# main.net
KiCad netlist of a schematic drawn in EAGLE
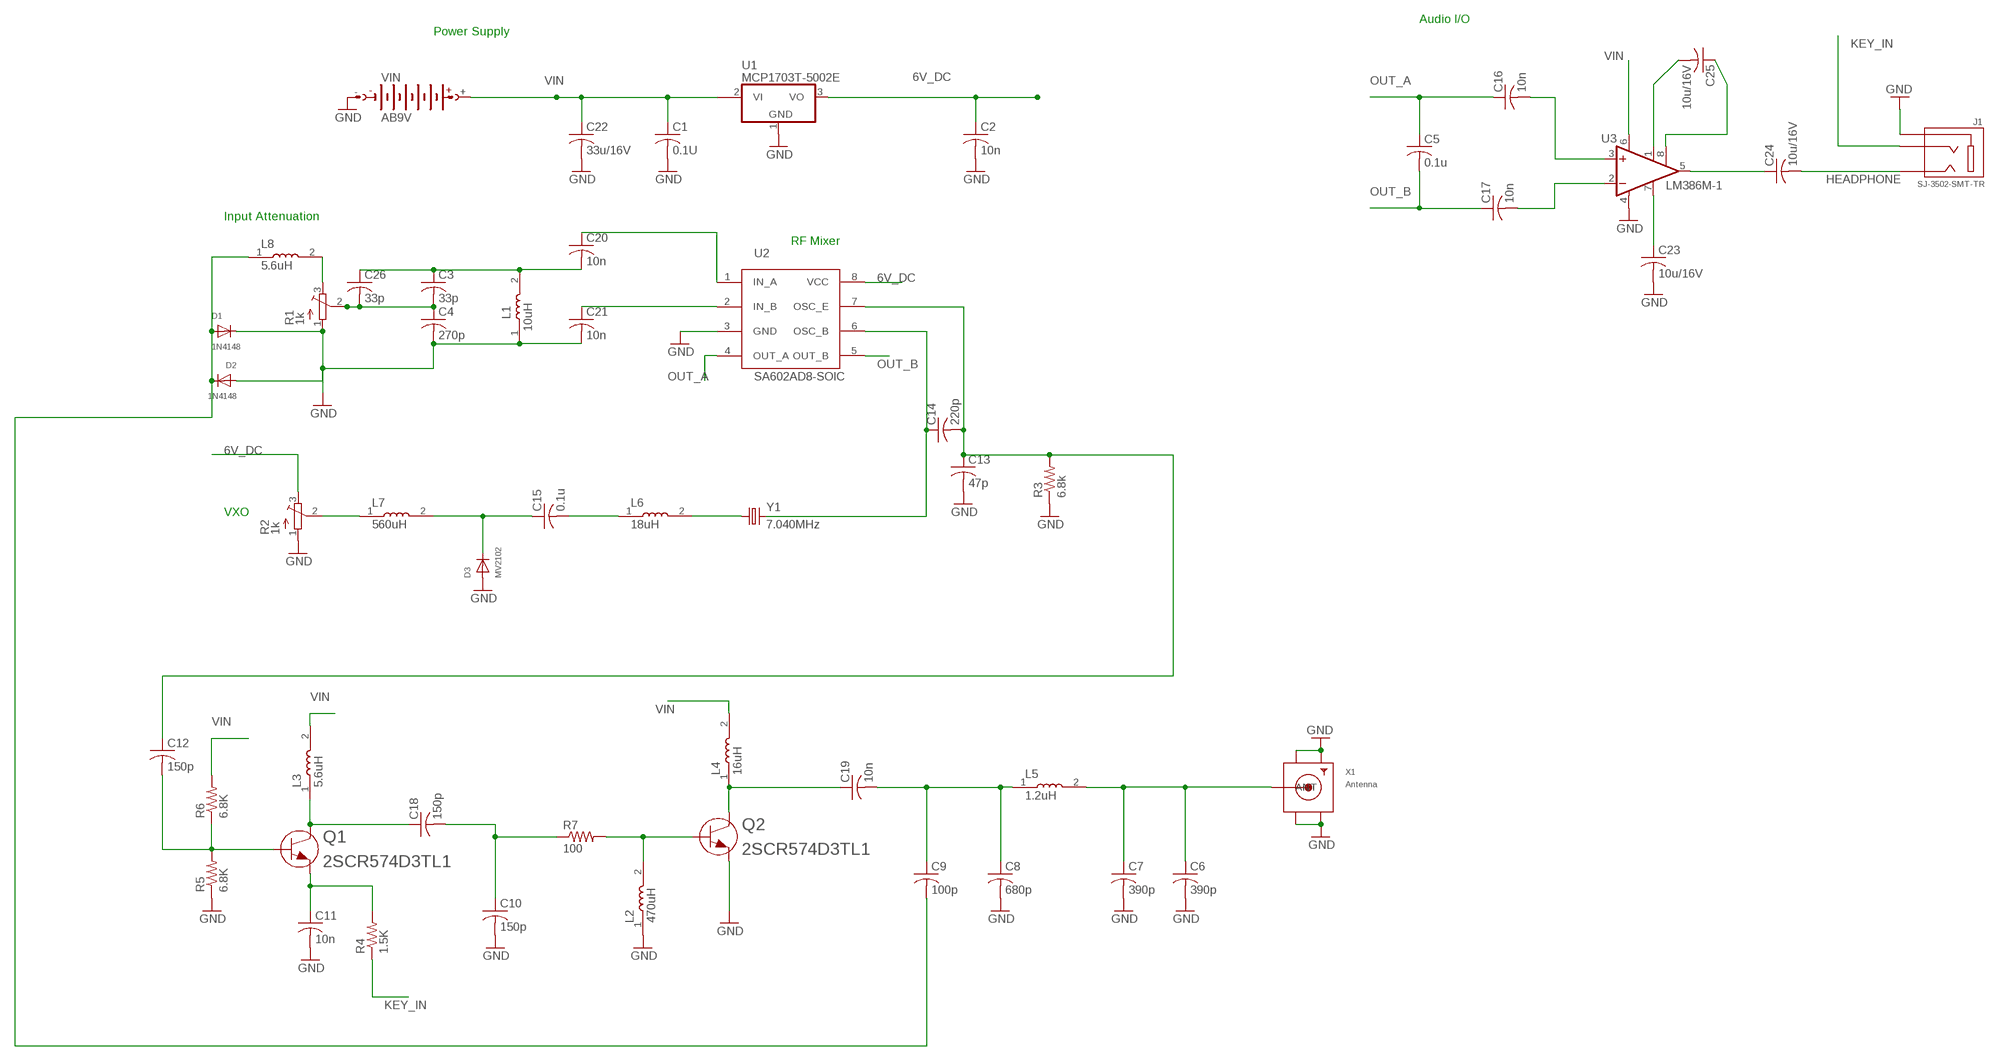
[diagram p0: schematic, sheet 1]

(export (version "E")
  (design (tool "Eeschema 10.0.6"))
  (components
    (comp (ref "C1")
      (value "0.1U")
      (footprint "eagle-import:C0805")
      (libsource (lib "eagle-import") (part "C-USC0805"))
    )
    (comp (ref "C2")
      (value "10n")
      (footprint "eagle-import:C0805")
      (libsource (lib "eagle-import") (part "C-USC0805"))
    )
    (comp (ref "C3")
      (value "33p")
      (footprint "eagle-import:C0805")
      (libsource (lib "eagle-import") (part "C-USC0805"))
    )
    (comp (ref "C4")
      (value "270p")
      (footprint "eagle-import:C0805")
      (libsource (lib "eagle-import") (part "C-USC0805"))
    )
    (comp (ref "C5")
      (value "0.1u")
      (footprint "eagle-import:C0805")
      (libsource (lib "eagle-import") (part "C-USC0805"))
    )
    (comp (ref "C6")
      (value "390p")
      (footprint "eagle-import:C0805")
      (libsource (lib "eagle-import") (part "C-USC0805"))
    )
    (comp (ref "C7")
      (value "390p")
      (footprint "eagle-import:C0805")
      (libsource (lib "eagle-import") (part "C-USC0805"))
    )
    (comp (ref "C8")
      (value "680p")
      (footprint "eagle-import:C0805")
      (libsource (lib "eagle-import") (part "C-USC0805"))
    )
    (comp (ref "C9")
      (value "100p")
      (footprint "eagle-import:C0805")
      (libsource (lib "eagle-import") (part "C-USC0805"))
    )
    (comp (ref "C10")
      (value "150p")
      (footprint "eagle-import:C0805")
      (libsource (lib "eagle-import") (part "C-USC0805"))
    )
    (comp (ref "C11")
      (value "10n")
      (footprint "eagle-import:C0805")
      (libsource (lib "eagle-import") (part "C-USC0805"))
    )
    (comp (ref "C12")
      (value "150p")
      (footprint "eagle-import:C0805")
      (libsource (lib "eagle-import") (part "C-USC0805"))
    )
    (comp (ref "C13")
      (value "47p")
      (footprint "eagle-import:C0805")
      (libsource (lib "eagle-import") (part "C-USC0805"))
    )
    (comp (ref "C14")
      (value "220p")
      (footprint "eagle-import:C0805")
      (libsource (lib "eagle-import") (part "C-USC0805"))
    )
    (comp (ref "C15")
      (value "0.1u")
      (footprint "eagle-import:C0805")
      (libsource (lib "eagle-import") (part "C-USC0805"))
    )
    (comp (ref "C16")
      (value "10n")
      (footprint "eagle-import:C0805")
      (libsource (lib "eagle-import") (part "C-USC0805"))
    )
    (comp (ref "C17")
      (value "10n")
      (footprint "eagle-import:C0805")
      (libsource (lib "eagle-import") (part "C-USC0805"))
    )
    (comp (ref "C18")
      (value "150p")
      (footprint "eagle-import:C0805")
      (libsource (lib "eagle-import") (part "C-USC0805"))
    )
    (comp (ref "C19")
      (value "10n")
      (footprint "eagle-import:C0805")
      (libsource (lib "eagle-import") (part "C-USC0805"))
    )
    (comp (ref "C20")
      (value "10n")
      (footprint "eagle-import:C0805")
      (libsource (lib "eagle-import") (part "C-USC0805"))
    )
    (comp (ref "C21")
      (value "10n")
      (footprint "eagle-import:C0805")
      (libsource (lib "eagle-import") (part "C-USC0805"))
    )
    (comp (ref "C22")
      (value "33u/16V")
      (footprint "eagle-import:C0805")
      (libsource (lib "eagle-import") (part "C-USC0805"))
    )
    (comp (ref "C23")
      (value "10u/16V")
      (footprint "eagle-import:C0805")
      (libsource (lib "eagle-import") (part "C-USC0805"))
    )
    (comp (ref "C24")
      (value "10u/16V")
      (footprint "eagle-import:C0805")
      (libsource (lib "eagle-import") (part "C-USC0805"))
    )
    (comp (ref "C25")
      (value "10u/16V")
      (footprint "eagle-import:C0805")
      (libsource (lib "eagle-import") (part "C-USC0805"))
    )
    (comp (ref "C26")
      (value "33p")
      (footprint "eagle-import:C0805")
      (libsource (lib "eagle-import") (part "C-USC0805"))
    )
    (comp (ref "D1")
      (value "1N4148")
      (footprint "eagle-import:SOD-123FL")
      (libsource (lib "eagle-import") (part "DIODE_SOD-123FL"))
    )
    (comp (ref "D2")
      (value "1N4148")
      (footprint "eagle-import:SOD-123FL")
      (libsource (lib "eagle-import") (part "DIODE_SOD-123FL"))
    )
    (comp (ref "D3")
      (value "MV2102")
      (footprint "eagle-import:SOD-323F")
      (libsource (lib "eagle-import") (part "DIODESOD-323F"))
    )
    (comp (ref "J1")
      (value "SJ-3502-SMT-TR")
      (footprint "eagle-import:SJ-3502-SMT-TR")
      (fields
        (field (name "DIGIKEY_PARTNO") "CP-3502SJTR-ND")
        (field (name "MANUFACTURER") "CUI Devices")
        (field (name "CREATED_BY") "PCBLayout.com")
      )
      (libsource (lib "eagle-import") (part "SJ-3502-SMT-TR"))
    )
    (comp (ref "L1")
      (value "10uH")
      (footprint "eagle-import:INDC2012X87N")
      (fields (field (name "MF") "TDK") (field (name "MP") "MLF2012E5R6KT000"))
      (libsource (lib "eagle-import") (part "MLF2012E5R6KT000"))
    )
    (comp (ref "L2")
      (value "470uH")
      (footprint "eagle-import:INDC2012X87N")
      (fields (field (name "MF") "TDK") (field (name "MP") "MLF2012E5R6KT000"))
      (libsource (lib "eagle-import") (part "MLF2012E5R6KT000"))
    )
    (comp (ref "L3")
      (value "5.6uH")
      (footprint "eagle-import:INDC2012X87N")
      (fields (field (name "MF") "TDK") (field (name "MP") "MLF2012E5R6KT000"))
      (libsource (lib "eagle-import") (part "MLF2012E5R6KT000"))
    )
    (comp (ref "L4")
      (value "16uH")
      (footprint "eagle-import:INDC2012X87N")
      (fields (field (name "MF") "TDK") (field (name "MP") "MLF2012E5R6KT000"))
      (libsource (lib "eagle-import") (part "MLF2012E5R6KT000"))
    )
    (comp (ref "L5")
      (value "1.2uH")
      (footprint "eagle-import:INDC2012X87N")
      (fields (field (name "MF") "TDK") (field (name "MP") "MLF2012E5R6KT000"))
      (libsource (lib "eagle-import") (part "MLF2012E5R6KT000"))
    )
    (comp (ref "L6")
      (value "18uH")
      (footprint "eagle-import:INDC2012X87N")
      (fields (field (name "MF") "TDK") (field (name "MP") "MLF2012E5R6KT000"))
      (libsource (lib "eagle-import") (part "MLF2012E5R6KT000"))
    )
    (comp (ref "L7")
      (value "560uH")
      (footprint "eagle-import:INDC2012X87N")
      (fields (field (name "MF") "TDK") (field (name "MP") "MLF2012E5R6KT000"))
      (libsource (lib "eagle-import") (part "MLF2012E5R6KT000"))
    )
    (comp (ref "L8")
      (value "5.6uH")
      (footprint "eagle-import:INDC2012X87N")
      (fields (field (name "MF") "TDK") (field (name "MP") "MLF2012E5R6KT000"))
      (libsource (lib "eagle-import") (part "MLF2012E5R6KT000"))
    )
    (comp (ref "Q1")
      (value "2SCR574D3TL1")
      (footprint "eagle-import:TRANS_2SCR573D_ROM")
      (fields (field (name "COPYRIGHT") "Copyright (C) 2018 Accelerated Designs. All rights reserved"))
      (libsource (lib "eagle-import") (part "2SCR574D3TL1"))
    )
    (comp (ref "Q2")
      (value "2SCR574D3TL1")
      (footprint "eagle-import:TRANS_2SCR573D_ROM")
      (fields (field (name "COPYRIGHT") "Copyright (C) 2018 Accelerated Designs. All rights reserved"))
      (libsource (lib "eagle-import") (part "2SCR574D3TL1"))
    )
    (comp (ref "R1")
      (value "1k")
      (footprint "eagle-import:3223G")
      (libsource (lib "eagle-import") (part "TRIM_EU-3223G"))
    )
    (comp (ref "R2")
      (value "1k")
      (footprint "eagle-import:3223G")
      (libsource (lib "eagle-import") (part "TRIM_EU-3223G"))
    )
    (comp (ref "R3")
      (value "6.8k")
      (footprint "eagle-import:M0805")
      (libsource (lib "eagle-import") (part "R-US_M0805"))
    )
    (comp (ref "R4")
      (value "1.5K")
      (footprint "eagle-import:M0805")
      (libsource (lib "eagle-import") (part "R-US_M0805"))
    )
    (comp (ref "R5")
      (value "6.8K")
      (footprint "eagle-import:M0805")
      (libsource (lib "eagle-import") (part "R-US_M0805"))
    )
    (comp (ref "R6")
      (value "6.8K")
      (footprint "eagle-import:M0805")
      (libsource (lib "eagle-import") (part "R-US_M0805"))
    )
    (comp (ref "R7")
      (value "100")
      (footprint "eagle-import:M0805")
      (libsource (lib "eagle-import") (part "R-US_M0805"))
    )
    (comp (ref "U1")
      (value "MCP1703T-5002E")
      (footprint "eagle-import:SOT89")
      (libsource (lib "eagle-import") (part "MCP1703MB12"))
    )
    (comp (ref "U2")
      (value "SA602AD8-SOIC")
      (footprint "eagle-import:SOIC127P599X175-8N")
      (libsource (lib "eagle-import") (part "SA602AD8-SOIC"))
    )
    (comp (ref "U3")
      (value "LM386M-1")
      (footprint "eagle-import:SO08")
      (libsource (lib "eagle-import") (part "LM386?-M1"))
    )
    (comp (ref "VIN")
      (value "AB9V")
      (footprint "eagle-import:AB9V")
      (libsource (lib "eagle-import") (part "AB9V"))
    )
    (comp (ref "X1")
      (value "Antenna")
      (footprint "eagle-import:SMA_EDGELAUNCH")
      (libsource (lib "eagle-import") (part "SMACONNECTOR_EDGE"))
    )
    (comp (ref "Y1")
      (value "7.040MHz")
      (footprint "eagle-import:CTS406")
      (libsource (lib "eagle-import") (part "CRYSTALCTS406"))
    )
  )
  (nets
    (net (code "1") (name "/6V_DC") (class "Default")
      (node (ref "C2") (pin "1") (pinfunction "1_1") (pintype "passive"))
      (node (ref "R2") (pin "3") (pinfunction "E_3") (pintype "passive"))
      (node (ref "U1") (pin "3") (pinfunction "VO_3") (pintype "passive"))
      (node (ref "U2") (pin "8") (pinfunction "VCC_8") (pintype "bidirectional"))
    )
    (net (code "2") (name "/HEADPHONE") (class "Default")
      (node (ref "C24") (pin "2") (pinfunction "2_2") (pintype "passive"))
      (node (ref "J1") (pin "2") (pinfunction "2_2") (pintype "passive"))
    )
    (net (code "3") (name "/KEY_IN") (class "Default")
      (node (ref "J1") (pin "3") (pinfunction "3_3") (pintype "passive"))
      (node (ref "R4") (pin "1") (pinfunction "1_1") (pintype "passive"))
    )
    (net (code "4") (name "/OUT_A") (class "Default")
      (node (ref "C16") (pin "1") (pinfunction "1_1") (pintype "passive"))
      (node (ref "C5") (pin "1") (pinfunction "1_1") (pintype "passive"))
      (node (ref "U2") (pin "4") (pinfunction "OUT_A_4") (pintype "bidirectional"))
    )
    (net (code "5") (name "/OUT_B") (class "Default")
      (node (ref "C17") (pin "1") (pinfunction "1_1") (pintype "passive"))
      (node (ref "C5") (pin "2") (pinfunction "2_2") (pintype "passive"))
      (node (ref "U2") (pin "5") (pinfunction "OUT_B_5") (pintype "bidirectional"))
    )
    (net (code "6") (name "/VIN") (class "Default")
      (node (ref "C1") (pin "1") (pinfunction "1_1") (pintype "passive"))
      (node (ref "C22") (pin "1") (pinfunction "1_1") (pintype "passive"))
      (node (ref "L3") (pin "2") (pinfunction "2_2") (pintype "passive"))
      (node (ref "L4") (pin "2") (pinfunction "2_2") (pintype "passive"))
      (node (ref "R6") (pin "2") (pinfunction "2_2") (pintype "passive"))
      (node (ref "U1") (pin "2@1") (pinfunction "VI1_2@1") (pintype "input"))
      (node (ref "U3") (pin "6") (pinfunction "VS_6") (pintype "power_in"))
      (node (ref "VIN") (pin "+") (pinfunction "+_+") (pintype "passive"))
    )
    (net (code "7") (name "GND") (class "Default")
      (node (ref "C1") (pin "2") (pinfunction "2_2") (pintype "passive"))
      (node (ref "C10") (pin "2") (pinfunction "2_2") (pintype "passive"))
      (node (ref "C11") (pin "2") (pinfunction "2_2") (pintype "passive"))
      (node (ref "C13") (pin "2") (pinfunction "2_2") (pintype "passive"))
      (node (ref "C2") (pin "2") (pinfunction "2_2") (pintype "passive"))
      (node (ref "C21") (pin "2") (pinfunction "2_2") (pintype "passive"))
      (node (ref "C22") (pin "2") (pinfunction "2_2") (pintype "passive"))
      (node (ref "C23") (pin "2") (pinfunction "2_2") (pintype "passive"))
      (node (ref "C4") (pin "2") (pinfunction "2_2") (pintype "passive"))
      (node (ref "C6") (pin "2") (pinfunction "2_2") (pintype "passive"))
      (node (ref "C7") (pin "2") (pinfunction "2_2") (pintype "passive"))
      (node (ref "C8") (pin "2") (pinfunction "2_2") (pintype "passive"))
      (node (ref "D1") (pin "C") (pinfunction "C_C") (pintype "passive"))
      (node (ref "D2") (pin "A") (pinfunction "A_A") (pintype "passive"))
      (node (ref "D3") (pin "A") (pinfunction "A_A") (pintype "passive"))
      (node (ref "J1") (pin "1_1") (pinfunction "1_1_1") (pintype "passive"))
      (node (ref "J1") (pin "1_2") (pinfunction "1_1_2") (pintype "passive"))
      (node (ref "J1") (pin "1_3") (pinfunction "1_1_3") (pintype "passive"))
      (node (ref "J1") (pin "1_4") (pinfunction "1_1_4") (pintype "passive"))
      (node (ref "L1") (pin "1") (pinfunction "1_1") (pintype "passive"))
      (node (ref "L2") (pin "1") (pinfunction "1_1") (pintype "passive"))
      (node (ref "Q2") (pin "3") (pinfunction "3_3") (pintype "passive"))
      (node (ref "R1") (pin "1") (pinfunction "A_1") (pintype "passive"))
      (node (ref "R2") (pin "1") (pinfunction "A_1") (pintype "passive"))
      (node (ref "R3") (pin "1") (pinfunction "1_1") (pintype "passive"))
      (node (ref "R5") (pin "1") (pinfunction "1_1") (pintype "passive"))
      (node (ref "U1") (pin "1") (pinfunction "GND_1") (pintype "passive"))
      (node (ref "U2") (pin "3") (pinfunction "GND_3") (pintype "bidirectional"))
      (node (ref "U3") (pin "4") (pinfunction "GND_4") (pintype "power_in"))
      (node (ref "VIN") (pin "-") (pinfunction "-_-") (pintype "passive"))
      (node (ref "X1") (pin "GND@1") (pinfunction "GND4_GND@1") (pintype "power_in"))
      (node (ref "X1") (pin "GND@2") (pinfunction "GND3_GND@2") (pintype "power_in"))
      (node (ref "X1") (pin "GND@3") (pinfunction "GND2_GND@3") (pintype "power_in"))
      (node (ref "X1") (pin "GND@4") (pinfunction "GND1_GND@4") (pintype "power_in"))
    )
    (net (code "8") (name "Net-(C9-Pad2)") (class "Default")
      (node (ref "C9") (pin "2") (pinfunction "2_2") (pintype "passive"))
      (node (ref "D1") (pin "A") (pinfunction "A_A") (pintype "passive"))
      (node (ref "D2") (pin "C") (pinfunction "C_C") (pintype "passive"))
      (node (ref "L8") (pin "1") (pinfunction "1_1") (pintype "passive"))
    )
    (net (code "9") (name "Net-(C10-Pad1)") (class "Default")
      (node (ref "C10") (pin "1") (pinfunction "1_1") (pintype "passive"))
      (node (ref "C18") (pin "2") (pinfunction "2_2") (pintype "passive"))
      (node (ref "R7") (pin "1") (pinfunction "1_1") (pintype "passive"))
    )
    (net (code "10") (name "Net-(C11-Pad1)") (class "Default")
      (node (ref "C11") (pin "1") (pinfunction "1_1") (pintype "passive"))
      (node (ref "Q1") (pin "3") (pinfunction "3_3") (pintype "passive"))
      (node (ref "R4") (pin "2") (pinfunction "2_2") (pintype "passive"))
    )
    (net (code "11") (name "Net-(C12-Pad2)") (class "Default")
      (node (ref "C12") (pin "2") (pinfunction "2_2") (pintype "passive"))
      (node (ref "Q1") (pin "1") (pinfunction "1_1") (pintype "passive"))
      (node (ref "R5") (pin "2") (pinfunction "2_2") (pintype "passive"))
      (node (ref "R6") (pin "1") (pinfunction "1_1") (pintype "passive"))
    )
    (net (code "12") (name "Net-(C15-Pad1)") (class "Default")
      (node (ref "C15") (pin "1") (pinfunction "1_1") (pintype "passive"))
      (node (ref "D3") (pin "C") (pinfunction "C_C") (pintype "passive"))
      (node (ref "L7") (pin "2") (pinfunction "2_2") (pintype "passive"))
    )
    (net (code "13") (name "Net-(C15-Pad2)") (class "Default")
      (node (ref "C15") (pin "2") (pinfunction "2_2") (pintype "passive"))
      (node (ref "L6") (pin "1") (pinfunction "1_1") (pintype "passive"))
    )
    (net (code "14") (name "Net-(C18-Pad1)") (class "Default")
      (node (ref "C18") (pin "1") (pinfunction "1_1") (pintype "passive"))
      (node (ref "L3") (pin "1") (pinfunction "1_1") (pintype "passive"))
      (node (ref "Q1") (pin "2") (pinfunction "2_2") (pintype "passive"))
    )
    (net (code "15") (name "Net-(C19-Pad1)") (class "Default")
      (node (ref "C19") (pin "1") (pinfunction "1_1") (pintype "passive"))
      (node (ref "L4") (pin "1") (pinfunction "1_1") (pintype "passive"))
      (node (ref "Q2") (pin "2") (pinfunction "2_2") (pintype "passive"))
    )
    (net (code "16") (name "Net-(C19-Pad2)") (class "Default")
      (node (ref "C19") (pin "2") (pinfunction "2_2") (pintype "passive"))
      (node (ref "C8") (pin "1") (pinfunction "1_1") (pintype "passive"))
      (node (ref "C9") (pin "1") (pinfunction "1_1") (pintype "passive"))
      (node (ref "L5") (pin "1") (pinfunction "1_1") (pintype "passive"))
    )
    (net (code "17") (name "Net-(C20-Pad2)") (class "Default")
      (node (ref "C20") (pin "2") (pinfunction "2_2") (pintype "passive"))
      (node (ref "C26") (pin "1") (pinfunction "1_1") (pintype "passive"))
      (node (ref "C3") (pin "1") (pinfunction "1_1") (pintype "passive"))
      (node (ref "L1") (pin "2") (pinfunction "2_2") (pintype "passive"))
    )
    (net (code "18") (name "Net-(C25-Pad1)") (class "Default")
      (node (ref "C25") (pin "1") (pinfunction "1_1") (pintype "passive"))
      (node (ref "U3") (pin "8") (pinfunction "GAIN_8") (pintype "passive"))
    )
    (net (code "19") (name "Net-(C25-Pad2)") (class "Default")
      (node (ref "C25") (pin "2") (pinfunction "2_2") (pintype "passive"))
      (node (ref "U3") (pin "1") (pinfunction "GAIN_1") (pintype "passive"))
    )
    (net (code "20") (name "Net-(L2-Pad2)") (class "Default")
      (node (ref "L2") (pin "2") (pinfunction "2_2") (pintype "passive"))
      (node (ref "Q2") (pin "1") (pinfunction "1_1") (pintype "passive"))
      (node (ref "R7") (pin "2") (pinfunction "2_2") (pintype "passive"))
    )
    (net (code "21") (name "Net-(L6-Pad2)") (class "Default")
      (node (ref "L6") (pin "2") (pinfunction "2_2") (pintype "passive"))
      (node (ref "Y1") (pin "1") (pinfunction "1_1") (pintype "passive"))
    )
    (net (code "22") (name "Net-(R1-E)") (class "Default")
      (node (ref "L8") (pin "2") (pinfunction "2_2") (pintype "passive"))
      (node (ref "R1") (pin "3") (pinfunction "E_3") (pintype "passive"))
    )
    (net (code "23") (name "Net-(R1-S)") (class "Default")
      (node (ref "C26") (pin "2") (pinfunction "2_2") (pintype "passive"))
      (node (ref "C3") (pin "2") (pinfunction "2_2") (pintype "passive"))
      (node (ref "C4") (pin "1") (pinfunction "1_1") (pintype "passive"))
      (node (ref "R1") (pin "2") (pinfunction "S_2") (pintype "passive"))
    )
    (net (code "24") (name "Net-(R2-S)") (class "Default")
      (node (ref "L7") (pin "1") (pinfunction "1_1") (pintype "passive"))
      (node (ref "R2") (pin "2") (pinfunction "S_2") (pintype "passive"))
    )
    (net (code "25") (name "Net-(U2-IN_A)") (class "Default")
      (node (ref "C20") (pin "1") (pinfunction "1_1") (pintype "passive"))
      (node (ref "U2") (pin "1") (pinfunction "IN_A_1") (pintype "bidirectional"))
    )
    (net (code "26") (name "Net-(U2-IN_B)") (class "Default")
      (node (ref "C21") (pin "1") (pinfunction "1_1") (pintype "passive"))
      (node (ref "U2") (pin "2") (pinfunction "IN_B_2") (pintype "bidirectional"))
    )
    (net (code "27") (name "Net-(U2-OSC_B)") (class "Default")
      (node (ref "C14") (pin "1") (pinfunction "1_1") (pintype "passive"))
      (node (ref "U2") (pin "6") (pinfunction "OSC_B_6") (pintype "bidirectional"))
      (node (ref "Y1") (pin "3") (pinfunction "2_3") (pintype "passive"))
    )
    (net (code "28") (name "Net-(U2-OSC_E)") (class "Default")
      (node (ref "C12") (pin "1") (pinfunction "1_1") (pintype "passive"))
      (node (ref "C13") (pin "1") (pinfunction "1_1") (pintype "passive"))
      (node (ref "C14") (pin "2") (pinfunction "2_2") (pintype "passive"))
      (node (ref "R3") (pin "2") (pinfunction "2_2") (pintype "passive"))
      (node (ref "U2") (pin "7") (pinfunction "OSC_E_7") (pintype "bidirectional"))
    )
    (net (code "29") (name "Net-(U3-+IN)") (class "Default")
      (node (ref "C16") (pin "2") (pinfunction "2_2") (pintype "passive"))
      (node (ref "U3") (pin "3") (pinfunction "+IN_3") (pintype "input"))
    )
    (net (code "30") (name "Net-(U3--IN)") (class "Default")
      (node (ref "C17") (pin "2") (pinfunction "2_2") (pintype "passive"))
      (node (ref "U3") (pin "2") (pinfunction "-IN_2") (pintype "input"))
    )
    (net (code "31") (name "Net-(U3-BYPASS)") (class "Default")
      (node (ref "C23") (pin "1") (pinfunction "1_1") (pintype "passive"))
      (node (ref "U3") (pin "7") (pinfunction "BYPASS_7") (pintype "passive"))
    )
    (net (code "32") (name "Net-(U3-OUT)") (class "Default")
      (node (ref "C24") (pin "1") (pinfunction "1_1") (pintype "passive"))
      (node (ref "U3") (pin "5") (pinfunction "OUT_5") (pintype "output"))
    )
    (net (code "33") (name "Net-(X1-ANT)") (class "Default")
      (node (ref "C6") (pin "1") (pinfunction "1_1") (pintype "passive"))
      (node (ref "C7") (pin "1") (pinfunction "1_1") (pintype "passive"))
      (node (ref "L5") (pin "2") (pinfunction "2_2") (pintype "passive"))
      (node (ref "X1") (pin "P") (pinfunction "ANT_P") (pintype "bidirectional"))
    )
    (net (code "34") (name "unconnected-(U1-VI-Pad2)") (class "Default")
      (node (ref "U1") (pin "2") (pinfunction "VI_2") (pintype "input"))
    )
  )
)
